# SKC_ErrrorDisplay.net
KiCad netlist of a schematic drawn in Altium Designer
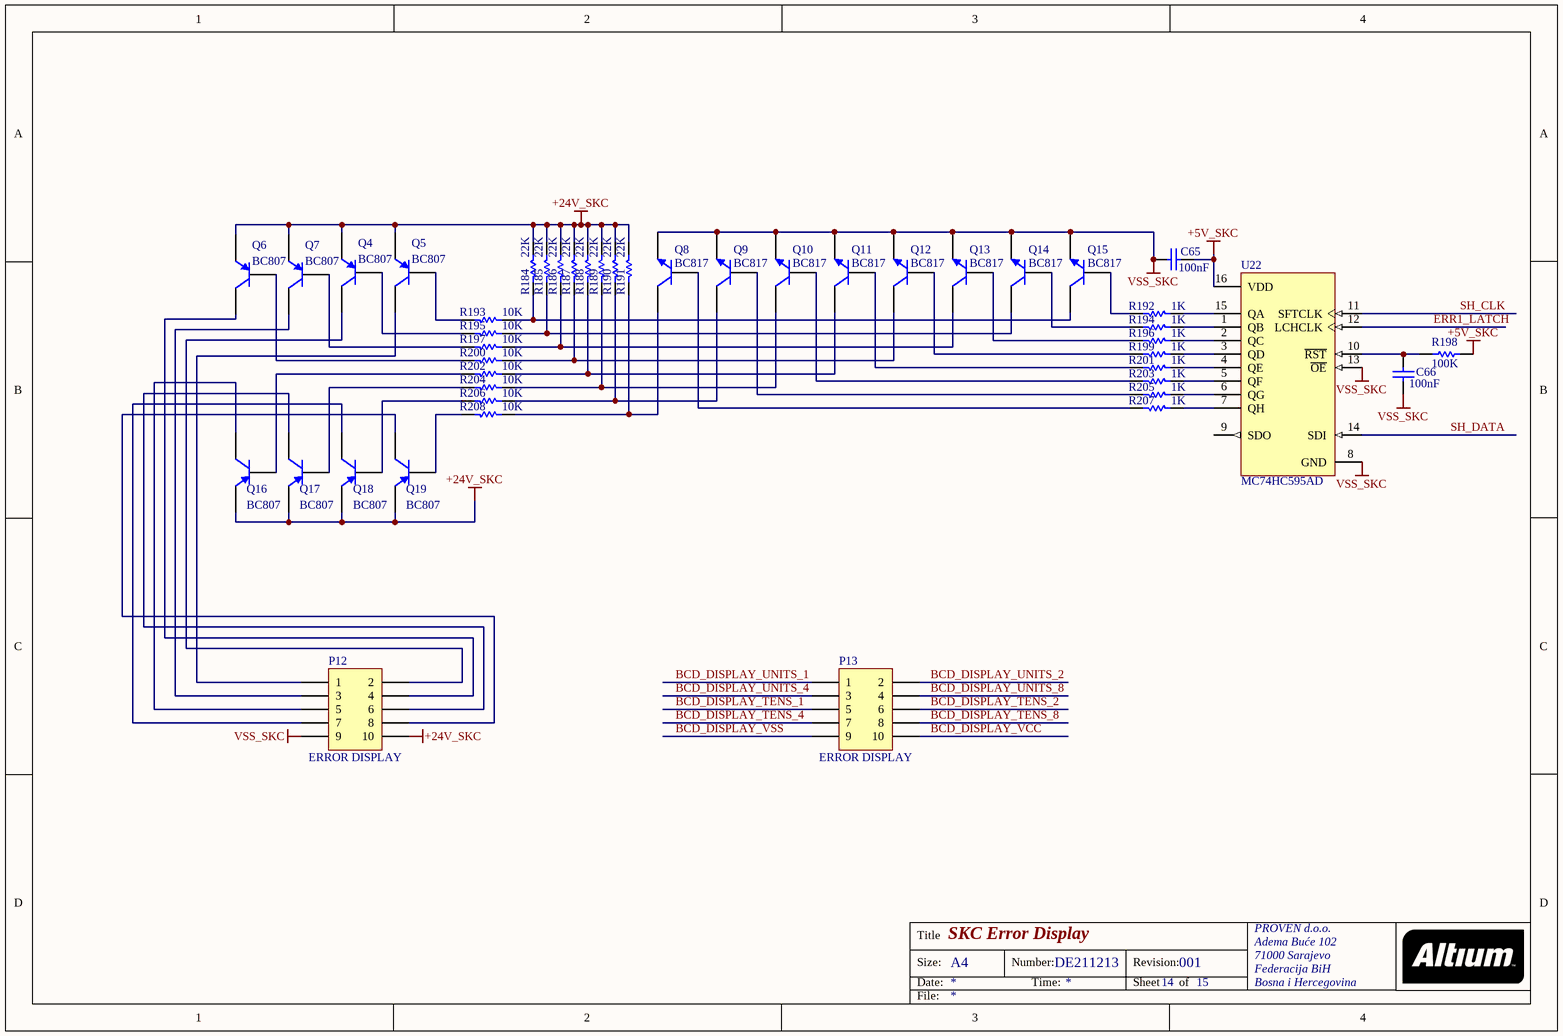
[diagram p0: SKC_ErrrorDisplay.SchDoc]

(export (version "E")
  (design (tool "Eeschema 10.0.6"))
  (components
    (comp (ref "C65")
      (value "100nF")
      (footprint "1206")
      (description "Ceramic Chip Capacitor - Standard")
      (fields (field (name "PUBLISHER") "Altium Limited"))
      (libsource (lib "KEMET Chip Capacitor") (part "C1206"))
    )
    (comp (ref "C66")
      (value "100nF")
      (footprint "1206")
      (description "Ceramic Chip Capacitor - Standard")
      (fields (field (name "PUBLISHER") "Altium Limited"))
      (libsource (lib "KEMET Chip Capacitor") (part "C1206"))
    )
    (comp (ref "P12")
      (value "ERROR DISPLAY")
      (footprint "HDR2X5")
      (description "Header, 5-Pin, Dual row")
      (fields (field (name "PUBLISHER") "Altium Limited"))
      (libsource (lib "Miscellaneous Connectors") (part "Header 5X2"))
    )
    (comp (ref "P13")
      (value "ERROR DISPLAY")
      (footprint "HDR2X5")
      (description "Header, 5-Pin, Dual row")
      (fields (field (name "PUBLISHER") "Altium Limited"))
      (libsource (lib "Miscellaneous Connectors") (part "Header 5X2"))
    )
    (comp (ref "Q4")
      (value "BC807")
      (footprint "SOT23_N")
      (description "PNP General-purpose Transistor")
      (fields (field (name "PUBLISHER") "Altium Limited"))
      (libsource (lib "Philips Discrete BJT - Low Power") (part "BC807"))
    )
    (comp (ref "Q5")
      (value "BC807")
      (footprint "SOT23_N")
      (description "PNP General-purpose Transistor")
      (fields (field (name "PUBLISHER") "Altium Limited"))
      (libsource (lib "Philips Discrete BJT - Low Power") (part "BC807"))
    )
    (comp (ref "Q6")
      (value "BC807")
      (footprint "SOT23_N")
      (description "PNP General-purpose Transistor")
      (fields (field (name "PUBLISHER") "Altium Limited"))
      (libsource (lib "Philips Discrete BJT - Low Power") (part "BC807"))
    )
    (comp (ref "Q7")
      (value "BC807")
      (footprint "SOT23_N")
      (description "PNP General-purpose Transistor")
      (fields (field (name "PUBLISHER") "Altium Limited"))
      (libsource (lib "Philips Discrete BJT - Low Power") (part "BC807"))
    )
    (comp (ref "Q8")
      (value "BC817")
      (footprint "SOT23_N")
      (description "NPN General-purpose Transistor")
      (fields (field (name "PUBLISHER") "Altium Limited"))
      (libsource (lib "Philips Discrete BJT - Low Power") (part "BC817-16"))
    )
    (comp (ref "Q9")
      (value "BC817")
      (footprint "SOT23_N")
      (description "NPN General-purpose Transistor")
      (fields (field (name "PUBLISHER") "Altium Limited"))
      (libsource (lib "Philips Discrete BJT - Low Power") (part "BC817-16"))
    )
    (comp (ref "Q10")
      (value "BC817")
      (footprint "SOT23_N")
      (description "NPN General-purpose Transistor")
      (fields (field (name "PUBLISHER") "Altium Limited"))
      (libsource (lib "Philips Discrete BJT - Low Power") (part "BC817-16"))
    )
    (comp (ref "Q11")
      (value "BC817")
      (footprint "SOT23_N")
      (description "NPN General-purpose Transistor")
      (fields (field (name "PUBLISHER") "Altium Limited"))
      (libsource (lib "Philips Discrete BJT - Low Power") (part "BC817-16"))
    )
    (comp (ref "Q12")
      (value "BC817")
      (footprint "SOT23_N")
      (description "NPN General-purpose Transistor")
      (fields (field (name "PUBLISHER") "Altium Limited"))
      (libsource (lib "Philips Discrete BJT - Low Power") (part "BC817-16"))
    )
    (comp (ref "Q13")
      (value "BC817")
      (footprint "SOT23_N")
      (description "NPN General-purpose Transistor")
      (fields (field (name "PUBLISHER") "Altium Limited"))
      (libsource (lib "Philips Discrete BJT - Low Power") (part "BC817-16"))
    )
    (comp (ref "Q14")
      (value "BC817")
      (footprint "SOT23_N")
      (description "NPN General-purpose Transistor")
      (fields (field (name "PUBLISHER") "Altium Limited"))
      (libsource (lib "Philips Discrete BJT - Low Power") (part "BC817-16"))
    )
    (comp (ref "Q15")
      (value "BC817")
      (footprint "SOT23_N")
      (description "NPN General-purpose Transistor")
      (fields (field (name "PUBLISHER") "Altium Limited"))
      (libsource (lib "Philips Discrete BJT - Low Power") (part "BC817-16"))
    )
    (comp (ref "Q16")
      (value "BC807")
      (footprint "SOT23_N")
      (description "PNP General-purpose Transistor")
      (fields (field (name "PUBLISHER") "Altium Limited"))
      (libsource (lib "Philips Discrete BJT - Low Power") (part "BC807"))
    )
    (comp (ref "Q17")
      (value "BC807")
      (footprint "SOT23_N")
      (description "PNP General-purpose Transistor")
      (fields (field (name "PUBLISHER") "Altium Limited"))
      (libsource (lib "Philips Discrete BJT - Low Power") (part "BC807"))
    )
    (comp (ref "Q18")
      (value "BC807")
      (footprint "SOT23_N")
      (description "PNP General-purpose Transistor")
      (fields (field (name "PUBLISHER") "Altium Limited"))
      (libsource (lib "Philips Discrete BJT - Low Power") (part "BC807"))
    )
    (comp (ref "Q19")
      (value "BC807")
      (footprint "SOT23_N")
      (description "PNP General-purpose Transistor")
      (fields (field (name "PUBLISHER") "Altium Limited"))
      (libsource (lib "Philips Discrete BJT - Low Power") (part "BC807"))
    )
    (comp (ref "R184")
      (value "22K")
      (footprint "ERA-0805")
      (fields (field (name "PUBLISHER") "Altium Limited"))
      (libsource (lib "Panasonic Resistor") (part "ERA6Y"))
    )
    (comp (ref "R185")
      (value "22K")
      (footprint "ERA-0805")
      (fields (field (name "PUBLISHER") "Altium Limited"))
      (libsource (lib "Panasonic Resistor") (part "ERA6Y"))
    )
    (comp (ref "R186")
      (value "22K")
      (footprint "ERA-0805")
      (fields (field (name "PUBLISHER") "Altium Limited"))
      (libsource (lib "Panasonic Resistor") (part "ERA6Y"))
    )
    (comp (ref "R187")
      (value "22K")
      (footprint "ERA-0805")
      (fields (field (name "PUBLISHER") "Altium Limited"))
      (libsource (lib "Panasonic Resistor") (part "ERA6Y"))
    )
    (comp (ref "R188")
      (value "22K")
      (footprint "ERA-0805")
      (fields (field (name "PUBLISHER") "Altium Limited"))
      (libsource (lib "Panasonic Resistor") (part "ERA6Y"))
    )
    (comp (ref "R189")
      (value "22K")
      (footprint "ERA-0805")
      (fields (field (name "PUBLISHER") "Altium Limited"))
      (libsource (lib "Panasonic Resistor") (part "ERA6Y"))
    )
    (comp (ref "R190")
      (value "22K")
      (footprint "ERA-0805")
      (fields (field (name "PUBLISHER") "Altium Limited"))
      (libsource (lib "Panasonic Resistor") (part "ERA6Y"))
    )
    (comp (ref "R191")
      (value "22K")
      (footprint "ERA-0805")
      (fields (field (name "PUBLISHER") "Altium Limited"))
      (libsource (lib "Panasonic Resistor") (part "ERA6Y"))
    )
    (comp (ref "R192")
      (value "1K")
      (footprint "ERA-0805")
      (fields (field (name "PUBLISHER") "Altium Limited"))
      (libsource (lib "Panasonic Resistor") (part "ERA6Y"))
    )
    (comp (ref "R193")
      (value "10K")
      (footprint "ERA-0805")
      (fields (field (name "PUBLISHER") "Altium Limited"))
      (libsource (lib "Panasonic Resistor") (part "ERA6Y"))
    )
    (comp (ref "R194")
      (value "1K")
      (footprint "ERA-0805")
      (fields (field (name "PUBLISHER") "Altium Limited"))
      (libsource (lib "Panasonic Resistor") (part "ERA6Y"))
    )
    (comp (ref "R195")
      (value "10K")
      (footprint "ERA-0805")
      (fields (field (name "PUBLISHER") "Altium Limited"))
      (libsource (lib "Panasonic Resistor") (part "ERA6Y"))
    )
    (comp (ref "R196")
      (value "1K")
      (footprint "ERA-0805")
      (fields (field (name "PUBLISHER") "Altium Limited"))
      (libsource (lib "Panasonic Resistor") (part "ERA6Y"))
    )
    (comp (ref "R197")
      (value "10K")
      (footprint "ERA-0805")
      (fields (field (name "PUBLISHER") "Altium Limited"))
      (libsource (lib "Panasonic Resistor") (part "ERA6Y"))
    )
    (comp (ref "R198")
      (value "100K")
      (footprint "ERA-0603")
      (fields (field (name "PUBLISHER") "Altium Limited"))
      (libsource (lib "Panasonic Resistor") (part "ERA3Y"))
    )
    (comp (ref "R199")
      (value "1K")
      (footprint "ERA-0805")
      (fields (field (name "PUBLISHER") "Altium Limited"))
      (libsource (lib "Panasonic Resistor") (part "ERA6Y"))
    )
    (comp (ref "R200")
      (value "10K")
      (footprint "ERA-0805")
      (fields (field (name "PUBLISHER") "Altium Limited"))
      (libsource (lib "Panasonic Resistor") (part "ERA6Y"))
    )
    (comp (ref "R201")
      (value "1K")
      (footprint "ERA-0805")
      (fields (field (name "PUBLISHER") "Altium Limited"))
      (libsource (lib "Panasonic Resistor") (part "ERA6Y"))
    )
    (comp (ref "R202")
      (value "10K")
      (footprint "ERA-0805")
      (fields (field (name "PUBLISHER") "Altium Limited"))
      (libsource (lib "Panasonic Resistor") (part "ERA6Y"))
    )
    (comp (ref "R203")
      (value "1K")
      (footprint "ERA-0805")
      (fields (field (name "PUBLISHER") "Altium Limited"))
      (libsource (lib "Panasonic Resistor") (part "ERA6Y"))
    )
    (comp (ref "R204")
      (value "10K")
      (footprint "ERA-0805")
      (fields (field (name "PUBLISHER") "Altium Limited"))
      (libsource (lib "Panasonic Resistor") (part "ERA6Y"))
    )
    (comp (ref "R205")
      (value "1K")
      (footprint "ERA-0805")
      (fields (field (name "PUBLISHER") "Altium Limited"))
      (libsource (lib "Panasonic Resistor") (part "ERA6Y"))
    )
    (comp (ref "R206")
      (value "10K")
      (footprint "ERA-0805")
      (fields (field (name "PUBLISHER") "Altium Limited"))
      (libsource (lib "Panasonic Resistor") (part "ERA6Y"))
    )
    (comp (ref "R207")
      (value "1K")
      (footprint "ERA-0805")
      (fields (field (name "PUBLISHER") "Altium Limited"))
      (libsource (lib "Panasonic Resistor") (part "ERA6Y"))
    )
    (comp (ref "R208")
      (value "10K")
      (footprint "ERA-0805")
      (fields (field (name "PUBLISHER") "Altium Limited"))
      (libsource (lib "Panasonic Resistor") (part "ERA6Y"))
    )
    (comp (ref "U22")
      (value "MC74HC595AD")
      (footprint "751B-05_N")
      (description "8-Bit Serial-Input/Serial or Prallel-Output Shift Register with Latched 3-State Outputs")
      (fields (field (name "PUBLISHER") "Altium Limited"))
      (libsource (lib "ON Semi Logic Register") (part "MC74HC595AD"))
    )
  )
  (nets
    (net (code "1") (name "+5V_SKC") (class "Default")
      (node (ref "C65") (pin "2") (pinfunction "2_2") (pintype "passive"))
      (node (ref "R198") (pin "2") (pinfunction "2_2") (pintype "passive"))
      (node (ref "U22") (pin "16") (pinfunction "VDD_16") (pintype "power_in"))
    )
    (net (code "2") (name "+24V_SKC") (class "Default")
      (node (ref "P12") (pin "10") (pinfunction "10_10") (pintype "passive"))
      (node (ref "Q16") (pin "2") (pinfunction "E_2") (pintype "passive"))
      (node (ref "Q17") (pin "2") (pinfunction "E_2") (pintype "passive"))
      (node (ref "Q18") (pin "2") (pinfunction "E_2") (pintype "passive"))
      (node (ref "Q19") (pin "2") (pinfunction "E_2") (pintype "passive"))
      (node (ref "Q4") (pin "2") (pinfunction "E_2") (pintype "passive"))
      (node (ref "Q5") (pin "2") (pinfunction "E_2") (pintype "passive"))
      (node (ref "Q6") (pin "2") (pinfunction "E_2") (pintype "passive"))
      (node (ref "Q7") (pin "2") (pinfunction "E_2") (pintype "passive"))
      (node (ref "R184") (pin "2") (pinfunction "2_2") (pintype "passive"))
      (node (ref "R185") (pin "2") (pinfunction "2_2") (pintype "passive"))
      (node (ref "R186") (pin "2") (pinfunction "2_2") (pintype "passive"))
      (node (ref "R187") (pin "2") (pinfunction "2_2") (pintype "passive"))
      (node (ref "R188") (pin "2") (pinfunction "2_2") (pintype "passive"))
      (node (ref "R189") (pin "2") (pinfunction "2_2") (pintype "passive"))
      (node (ref "R190") (pin "2") (pinfunction "2_2") (pintype "passive"))
      (node (ref "R191") (pin "2") (pinfunction "2_2") (pintype "passive"))
    )
    (net (code "3") (name "/BCD_DISPLAY_TENS_1") (class "Default")
      (node (ref "P13") (pin "5") (pinfunction "5_5") (pintype "passive"))
    )
    (net (code "4") (name "/BCD_DISPLAY_TENS_2") (class "Default")
      (node (ref "P13") (pin "6") (pinfunction "6_6") (pintype "passive"))
    )
    (net (code "5") (name "/BCD_DISPLAY_TENS_4") (class "Default")
      (node (ref "P13") (pin "7") (pinfunction "7_7") (pintype "passive"))
    )
    (net (code "6") (name "/BCD_DISPLAY_TENS_8") (class "Default")
      (node (ref "P13") (pin "8") (pinfunction "8_8") (pintype "passive"))
    )
    (net (code "7") (name "/BCD_DISPLAY_UNITS_1") (class "Default")
      (node (ref "P13") (pin "1") (pinfunction "1_1") (pintype "passive"))
    )
    (net (code "8") (name "/BCD_DISPLAY_UNITS_2") (class "Default")
      (node (ref "P13") (pin "2") (pinfunction "2_2") (pintype "passive"))
    )
    (net (code "9") (name "/BCD_DISPLAY_UNITS_4") (class "Default")
      (node (ref "P13") (pin "3") (pinfunction "3_3") (pintype "passive"))
    )
    (net (code "10") (name "/BCD_DISPLAY_UNITS_8") (class "Default")
      (node (ref "P13") (pin "4") (pinfunction "4_4") (pintype "passive"))
    )
    (net (code "11") (name "/BCD_DISPLAY_VCC") (class "Default")
      (node (ref "P13") (pin "10") (pinfunction "10_10") (pintype "passive"))
    )
    (net (code "12") (name "/BCD_DISPLAY_VSS") (class "Default")
      (node (ref "P13") (pin "9") (pinfunction "9_9") (pintype "passive"))
    )
    (net (code "13") (name "/ERR1_LATCH") (class "Default")
      (node (ref "U22") (pin "12") (pinfunction "LCHCLK_12") (pintype "input"))
    )
    (net (code "14") (name "/SH_CLK") (class "Default")
      (node (ref "U22") (pin "11") (pinfunction "SFTCLK_11") (pintype "input"))
    )
    (net (code "15") (name "/SH_DATA") (class "Default")
      (node (ref "U22") (pin "14") (pinfunction "SDI_14") (pintype "input"))
    )
    (net (code "16") (name "Net-(Q4-B)") (class "Default")
      (node (ref "Q4") (pin "1") (pinfunction "B_1") (pintype "passive"))
      (node (ref "R195") (pin "1") (pinfunction "1_1") (pintype "passive"))
    )
    (net (code "17") (name "Net-(Q4-C)") (class "Default")
      (node (ref "P12") (pin "2") (pinfunction "2_2") (pintype "passive"))
      (node (ref "Q4") (pin "3") (pinfunction "C_3") (pintype "passive"))
    )
    (net (code "18") (name "Net-(Q5-B)") (class "Default")
      (node (ref "Q5") (pin "1") (pinfunction "B_1") (pintype "passive"))
      (node (ref "R193") (pin "1") (pinfunction "1_1") (pintype "passive"))
    )
    (net (code "19") (name "Net-(Q5-C)") (class "Default")
      (node (ref "P12") (pin "1") (pinfunction "1_1") (pintype "passive"))
      (node (ref "Q5") (pin "3") (pinfunction "C_3") (pintype "passive"))
    )
    (net (code "20") (name "Net-(Q6-B)") (class "Default")
      (node (ref "Q6") (pin "1") (pinfunction "B_1") (pintype "passive"))
      (node (ref "R200") (pin "1") (pinfunction "1_1") (pintype "passive"))
    )
    (net (code "21") (name "Net-(Q6-C)") (class "Default")
      (node (ref "P12") (pin "4") (pinfunction "4_4") (pintype "passive"))
      (node (ref "Q6") (pin "3") (pinfunction "C_3") (pintype "passive"))
    )
    (net (code "22") (name "Net-(Q7-B)") (class "Default")
      (node (ref "Q7") (pin "1") (pinfunction "B_1") (pintype "passive"))
      (node (ref "R197") (pin "1") (pinfunction "1_1") (pintype "passive"))
    )
    (net (code "23") (name "Net-(Q7-C)") (class "Default")
      (node (ref "P12") (pin "3") (pinfunction "3_3") (pintype "passive"))
      (node (ref "Q7") (pin "3") (pinfunction "C_3") (pintype "passive"))
    )
    (net (code "24") (name "Net-(Q8-B)") (class "Default")
      (node (ref "Q8") (pin "1") (pinfunction "B_1") (pintype "passive"))
      (node (ref "R207") (pin "1") (pinfunction "1_1") (pintype "passive"))
    )
    (net (code "25") (name "Net-(Q8-C)") (class "Default")
      (node (ref "Q8") (pin "3") (pinfunction "C_3") (pintype "passive"))
      (node (ref "R191") (pin "1") (pinfunction "1_1") (pintype "passive"))
      (node (ref "R208") (pin "2") (pinfunction "2_2") (pintype "passive"))
    )
    (net (code "26") (name "Net-(Q9-B)") (class "Default")
      (node (ref "Q9") (pin "1") (pinfunction "B_1") (pintype "passive"))
      (node (ref "R205") (pin "1") (pinfunction "1_1") (pintype "passive"))
    )
    (net (code "27") (name "Net-(Q9-C)") (class "Default")
      (node (ref "Q9") (pin "3") (pinfunction "C_3") (pintype "passive"))
      (node (ref "R190") (pin "1") (pinfunction "1_1") (pintype "passive"))
      (node (ref "R206") (pin "2") (pinfunction "2_2") (pintype "passive"))
    )
    (net (code "28") (name "Net-(Q10-B)") (class "Default")
      (node (ref "Q10") (pin "1") (pinfunction "B_1") (pintype "passive"))
      (node (ref "R203") (pin "1") (pinfunction "1_1") (pintype "passive"))
    )
    (net (code "29") (name "Net-(Q10-C)") (class "Default")
      (node (ref "Q10") (pin "3") (pinfunction "C_3") (pintype "passive"))
      (node (ref "R189") (pin "1") (pinfunction "1_1") (pintype "passive"))
      (node (ref "R204") (pin "2") (pinfunction "2_2") (pintype "passive"))
    )
    (net (code "30") (name "Net-(Q11-B)") (class "Default")
      (node (ref "Q11") (pin "1") (pinfunction "B_1") (pintype "passive"))
      (node (ref "R201") (pin "1") (pinfunction "1_1") (pintype "passive"))
    )
    (net (code "31") (name "Net-(Q11-C)") (class "Default")
      (node (ref "Q11") (pin "3") (pinfunction "C_3") (pintype "passive"))
      (node (ref "R188") (pin "1") (pinfunction "1_1") (pintype "passive"))
      (node (ref "R202") (pin "2") (pinfunction "2_2") (pintype "passive"))
    )
    (net (code "32") (name "Net-(Q12-B)") (class "Default")
      (node (ref "Q12") (pin "1") (pinfunction "B_1") (pintype "passive"))
      (node (ref "R199") (pin "1") (pinfunction "1_1") (pintype "passive"))
    )
    (net (code "33") (name "Net-(Q12-C)") (class "Default")
      (node (ref "Q12") (pin "3") (pinfunction "C_3") (pintype "passive"))
      (node (ref "R187") (pin "1") (pinfunction "1_1") (pintype "passive"))
      (node (ref "R200") (pin "2") (pinfunction "2_2") (pintype "passive"))
    )
    (net (code "34") (name "Net-(Q13-B)") (class "Default")
      (node (ref "Q13") (pin "1") (pinfunction "B_1") (pintype "passive"))
      (node (ref "R196") (pin "1") (pinfunction "1_1") (pintype "passive"))
    )
    (net (code "35") (name "Net-(Q13-C)") (class "Default")
      (node (ref "Q13") (pin "3") (pinfunction "C_3") (pintype "passive"))
      (node (ref "R186") (pin "1") (pinfunction "1_1") (pintype "passive"))
      (node (ref "R197") (pin "2") (pinfunction "2_2") (pintype "passive"))
    )
    (net (code "36") (name "Net-(Q14-B)") (class "Default")
      (node (ref "Q14") (pin "1") (pinfunction "B_1") (pintype "passive"))
      (node (ref "R194") (pin "1") (pinfunction "1_1") (pintype "passive"))
    )
    (net (code "37") (name "Net-(Q14-C)") (class "Default")
      (node (ref "Q14") (pin "3") (pinfunction "C_3") (pintype "passive"))
      (node (ref "R185") (pin "1") (pinfunction "1_1") (pintype "passive"))
      (node (ref "R195") (pin "2") (pinfunction "2_2") (pintype "passive"))
    )
    (net (code "38") (name "Net-(Q15-B)") (class "Default")
      (node (ref "Q15") (pin "1") (pinfunction "B_1") (pintype "passive"))
      (node (ref "R192") (pin "1") (pinfunction "1_1") (pintype "passive"))
    )
    (net (code "39") (name "Net-(Q15-C)") (class "Default")
      (node (ref "Q15") (pin "3") (pinfunction "C_3") (pintype "passive"))
      (node (ref "R184") (pin "1") (pinfunction "1_1") (pintype "passive"))
      (node (ref "R193") (pin "2") (pinfunction "2_2") (pintype "passive"))
    )
    (net (code "40") (name "Net-(Q16-B)") (class "Default")
      (node (ref "Q16") (pin "1") (pinfunction "B_1") (pintype "passive"))
      (node (ref "R202") (pin "1") (pinfunction "1_1") (pintype "passive"))
    )
    (net (code "41") (name "Net-(Q16-C)") (class "Default")
      (node (ref "P12") (pin "5") (pinfunction "5_5") (pintype "passive"))
      (node (ref "Q16") (pin "3") (pinfunction "C_3") (pintype "passive"))
    )
    (net (code "42") (name "Net-(Q17-B)") (class "Default")
      (node (ref "Q17") (pin "1") (pinfunction "B_1") (pintype "passive"))
      (node (ref "R204") (pin "1") (pinfunction "1_1") (pintype "passive"))
    )
    (net (code "43") (name "Net-(Q17-C)") (class "Default")
      (node (ref "P12") (pin "6") (pinfunction "6_6") (pintype "passive"))
      (node (ref "Q17") (pin "3") (pinfunction "C_3") (pintype "passive"))
    )
    (net (code "44") (name "Net-(Q18-B)") (class "Default")
      (node (ref "Q18") (pin "1") (pinfunction "B_1") (pintype "passive"))
      (node (ref "R206") (pin "1") (pinfunction "1_1") (pintype "passive"))
    )
    (net (code "45") (name "Net-(Q18-C)") (class "Default")
      (node (ref "P12") (pin "7") (pinfunction "7_7") (pintype "passive"))
      (node (ref "Q18") (pin "3") (pinfunction "C_3") (pintype "passive"))
    )
    (net (code "46") (name "Net-(Q19-B)") (class "Default")
      (node (ref "Q19") (pin "1") (pinfunction "B_1") (pintype "passive"))
      (node (ref "R208") (pin "1") (pinfunction "1_1") (pintype "passive"))
    )
    (net (code "47") (name "Net-(Q19-C)") (class "Default")
      (node (ref "P12") (pin "8") (pinfunction "8_8") (pintype "passive"))
      (node (ref "Q19") (pin "3") (pinfunction "C_3") (pintype "passive"))
    )
    (net (code "48") (name "Net-(U22-QA)") (class "Default")
      (node (ref "R192") (pin "2") (pinfunction "2_2") (pintype "passive"))
      (node (ref "U22") (pin "15") (pinfunction "QA_15") (pintype "tri_state"))
    )
    (net (code "49") (name "Net-(U22-QB)") (class "Default")
      (node (ref "R194") (pin "2") (pinfunction "2_2") (pintype "passive"))
      (node (ref "U22") (pin "1") (pinfunction "QB_1") (pintype "tri_state"))
    )
    (net (code "50") (name "Net-(U22-QC)") (class "Default")
      (node (ref "R196") (pin "2") (pinfunction "2_2") (pintype "passive"))
      (node (ref "U22") (pin "2") (pinfunction "QC_2") (pintype "tri_state"))
    )
    (net (code "51") (name "Net-(U22-QD)") (class "Default")
      (node (ref "R199") (pin "2") (pinfunction "2_2") (pintype "passive"))
      (node (ref "U22") (pin "3") (pinfunction "QD_3") (pintype "tri_state"))
    )
    (net (code "52") (name "Net-(U22-QE)") (class "Default")
      (node (ref "R201") (pin "2") (pinfunction "2_2") (pintype "passive"))
      (node (ref "U22") (pin "4") (pinfunction "QE_4") (pintype "tri_state"))
    )
    (net (code "53") (name "Net-(U22-QF)") (class "Default")
      (node (ref "R203") (pin "2") (pinfunction "2_2") (pintype "passive"))
      (node (ref "U22") (pin "5") (pinfunction "QF_5") (pintype "tri_state"))
    )
    (net (code "54") (name "Net-(U22-QG)") (class "Default")
      (node (ref "R205") (pin "2") (pinfunction "2_2") (pintype "passive"))
      (node (ref "U22") (pin "6") (pinfunction "QG_6") (pintype "tri_state"))
    )
    (net (code "55") (name "Net-(U22-QH)") (class "Default")
      (node (ref "R207") (pin "2") (pinfunction "2_2") (pintype "passive"))
      (node (ref "U22") (pin "7") (pinfunction "QH_7") (pintype "tri_state"))
    )
    (net (code "56") (name "Net-(U22-~{RST})") (class "Default")
      (node (ref "C66") (pin "2") (pinfunction "2_2") (pintype "passive"))
      (node (ref "R198") (pin "1") (pinfunction "1_1") (pintype "passive"))
      (node (ref "U22") (pin "10") (pinfunction "~{RST}_10") (pintype "input"))
    )
    (net (code "57") (name "VSS_SKC") (class "Default")
      (node (ref "C65") (pin "1") (pinfunction "1_1") (pintype "passive"))
      (node (ref "C66") (pin "1") (pinfunction "1_1") (pintype "passive"))
      (node (ref "P12") (pin "9") (pinfunction "9_9") (pintype "passive"))
      (node (ref "Q10") (pin "2") (pinfunction "E_2") (pintype "passive"))
      (node (ref "Q11") (pin "2") (pinfunction "E_2") (pintype "passive"))
      (node (ref "Q12") (pin "2") (pinfunction "E_2") (pintype "passive"))
      (node (ref "Q13") (pin "2") (pinfunction "E_2") (pintype "passive"))
      (node (ref "Q14") (pin "2") (pinfunction "E_2") (pintype "passive"))
      (node (ref "Q15") (pin "2") (pinfunction "E_2") (pintype "passive"))
      (node (ref "Q8") (pin "2") (pinfunction "E_2") (pintype "passive"))
      (node (ref "Q9") (pin "2") (pinfunction "E_2") (pintype "passive"))
      (node (ref "U22") (pin "13") (pinfunction "~{OE}_13") (pintype "input"))
      (node (ref "U22") (pin "8") (pinfunction "GND_8") (pintype "power_in"))
    )
    (net (code "58") (name "unconnected-(U22-SDO-Pad9)") (class "Default")
      (node (ref "U22") (pin "9") (pinfunction "SDO_9") (pintype "output"))
    )
  )
)
